# config.net
KiCad netlist of a schematic drawn in Altium Designer
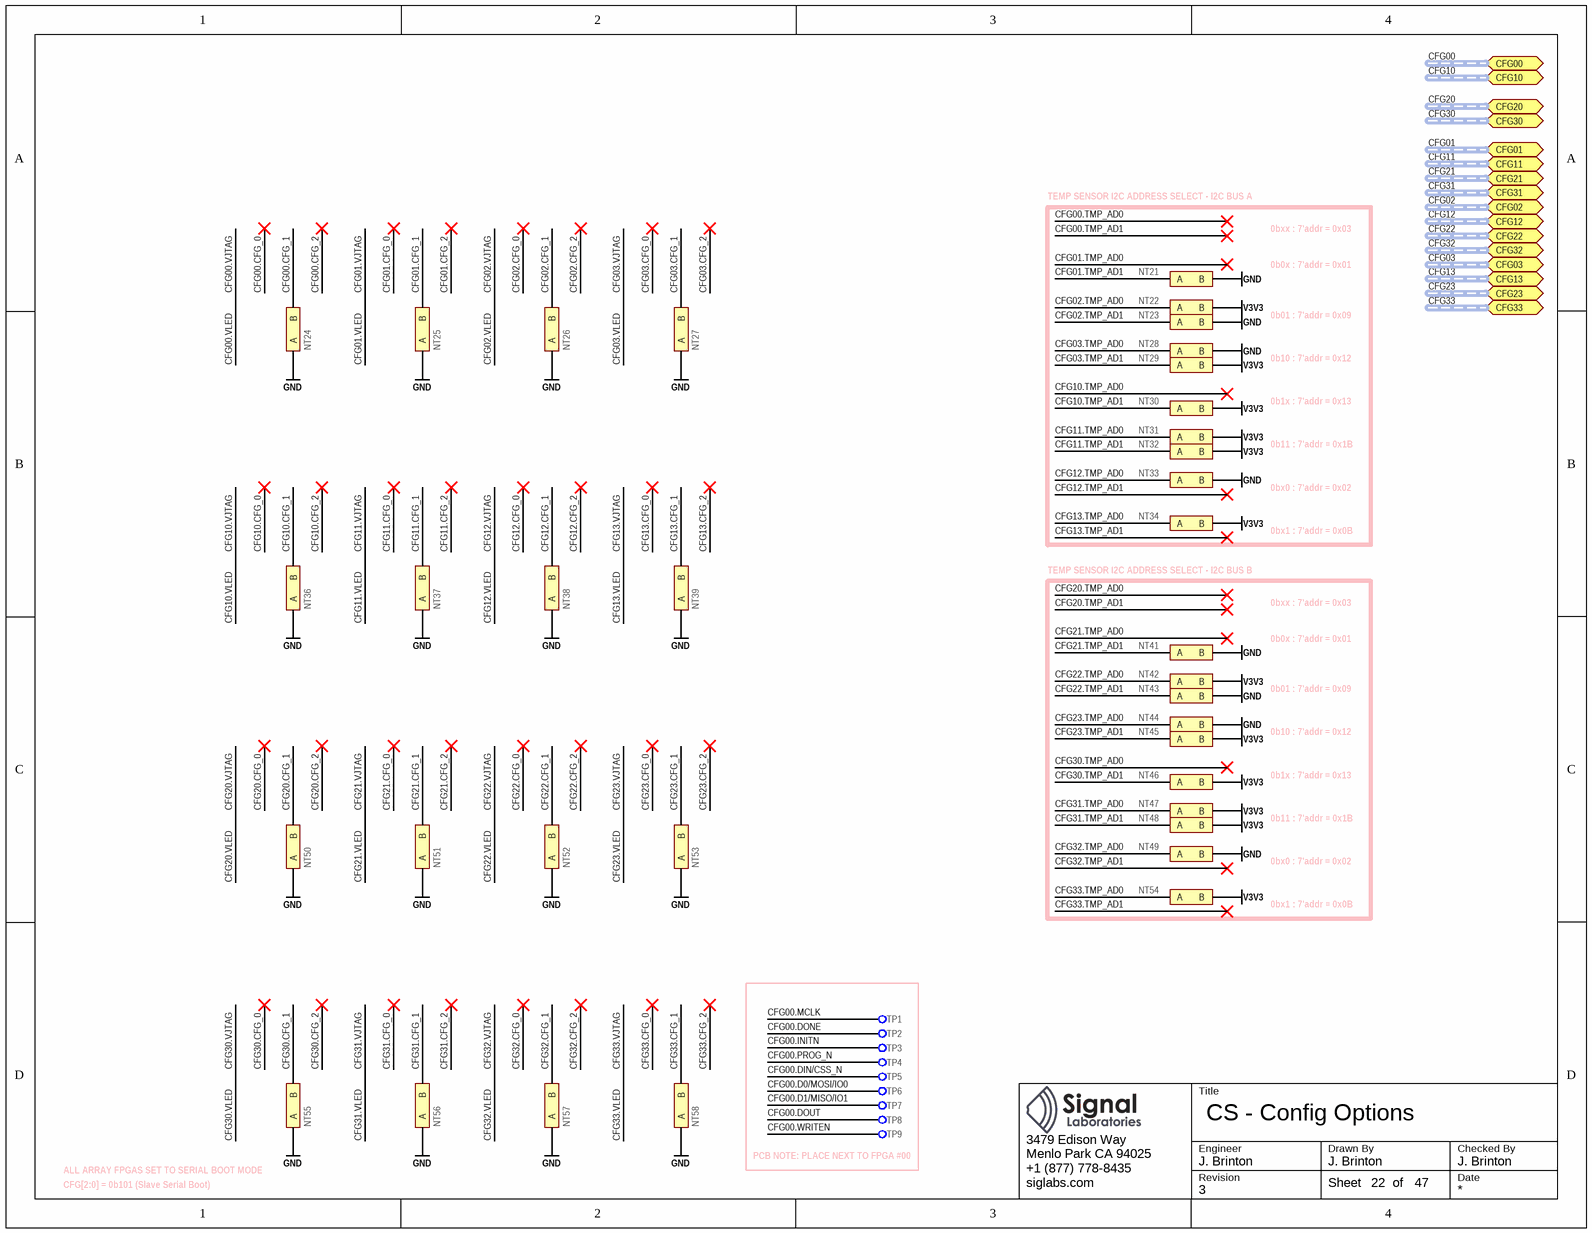
[diagram p0: config.SchDoc]

(export (version "E")
  (design (tool "Eeschema 10.0.6"))
  (components
    (comp (ref "NT21")
      (value "NET_TIE")
      (footprint "NET_TIE")
      (libsource (lib "copper_suicide") (part "NET_TIE"))
    )
    (comp (ref "NT22")
      (value "NET_TIE")
      (footprint "NET_TIE")
      (libsource (lib "copper_suicide") (part "NET_TIE"))
    )
    (comp (ref "NT23")
      (value "NET_TIE")
      (footprint "NET_TIE")
      (libsource (lib "copper_suicide") (part "NET_TIE"))
    )
    (comp (ref "NT24") (value "NET_TIE") (footprint "NET_TIE_400") (libsource (lib "") (part "NET_TIE_1")))
    (comp (ref "NT25") (value "NET_TIE") (footprint "NET_TIE_400") (libsource (lib "") (part "NET_TIE_1")))
    (comp (ref "NT26") (value "NET_TIE") (footprint "NET_TIE_400") (libsource (lib "") (part "NET_TIE_1")))
    (comp (ref "NT27") (value "NET_TIE") (footprint "NET_TIE_400") (libsource (lib "") (part "NET_TIE_1")))
    (comp (ref "NT28")
      (value "NET_TIE")
      (footprint "NET_TIE")
      (libsource (lib "copper_suicide") (part "NET_TIE"))
    )
    (comp (ref "NT29")
      (value "NET_TIE")
      (footprint "NET_TIE")
      (libsource (lib "copper_suicide") (part "NET_TIE"))
    )
    (comp (ref "NT30")
      (value "NET_TIE")
      (footprint "NET_TIE")
      (libsource (lib "copper_suicide") (part "NET_TIE"))
    )
    (comp (ref "NT31")
      (value "NET_TIE")
      (footprint "NET_TIE")
      (libsource (lib "copper_suicide") (part "NET_TIE"))
    )
    (comp (ref "NT32")
      (value "NET_TIE")
      (footprint "NET_TIE")
      (libsource (lib "copper_suicide") (part "NET_TIE"))
    )
    (comp (ref "NT33")
      (value "NET_TIE")
      (footprint "NET_TIE")
      (libsource (lib "copper_suicide") (part "NET_TIE"))
    )
    (comp (ref "NT34")
      (value "NET_TIE")
      (footprint "NET_TIE")
      (libsource (lib "copper_suicide") (part "NET_TIE"))
    )
    (comp (ref "NT36") (value "NET_TIE") (footprint "NET_TIE_400") (libsource (lib "") (part "NET_TIE_1")))
    (comp (ref "NT37") (value "NET_TIE") (footprint "NET_TIE_400") (libsource (lib "") (part "NET_TIE_1")))
    (comp (ref "NT38") (value "NET_TIE") (footprint "NET_TIE_400") (libsource (lib "") (part "NET_TIE_1")))
    (comp (ref "NT39") (value "NET_TIE") (footprint "NET_TIE_400") (libsource (lib "") (part "NET_TIE_1")))
    (comp (ref "NT41")
      (value "NET_TIE")
      (footprint "NET_TIE")
      (libsource (lib "copper_suicide") (part "NET_TIE"))
    )
    (comp (ref "NT42")
      (value "NET_TIE")
      (footprint "NET_TIE")
      (libsource (lib "copper_suicide") (part "NET_TIE"))
    )
    (comp (ref "NT43")
      (value "NET_TIE")
      (footprint "NET_TIE")
      (libsource (lib "copper_suicide") (part "NET_TIE"))
    )
    (comp (ref "NT44")
      (value "NET_TIE")
      (footprint "NET_TIE")
      (libsource (lib "copper_suicide") (part "NET_TIE"))
    )
    (comp (ref "NT45")
      (value "NET_TIE")
      (footprint "NET_TIE")
      (libsource (lib "copper_suicide") (part "NET_TIE"))
    )
    (comp (ref "NT46")
      (value "NET_TIE")
      (footprint "NET_TIE")
      (libsource (lib "copper_suicide") (part "NET_TIE"))
    )
    (comp (ref "NT47")
      (value "NET_TIE")
      (footprint "NET_TIE")
      (libsource (lib "copper_suicide") (part "NET_TIE"))
    )
    (comp (ref "NT48")
      (value "NET_TIE")
      (footprint "NET_TIE")
      (libsource (lib "copper_suicide") (part "NET_TIE"))
    )
    (comp (ref "NT49")
      (value "NET_TIE")
      (footprint "NET_TIE")
      (libsource (lib "copper_suicide") (part "NET_TIE"))
    )
    (comp (ref "NT50") (value "NET_TIE") (footprint "NET_TIE_400") (libsource (lib "") (part "NET_TIE_1")))
    (comp (ref "NT51") (value "NET_TIE") (footprint "NET_TIE_400") (libsource (lib "") (part "NET_TIE_1")))
    (comp (ref "NT52") (value "NET_TIE") (footprint "NET_TIE_400") (libsource (lib "") (part "NET_TIE_1")))
    (comp (ref "NT53") (value "NET_TIE") (footprint "NET_TIE_400") (libsource (lib "") (part "NET_TIE_1")))
    (comp (ref "NT54")
      (value "NET_TIE")
      (footprint "NET_TIE")
      (libsource (lib "copper_suicide") (part "NET_TIE"))
    )
    (comp (ref "NT55") (value "NET_TIE") (footprint "NET_TIE_400") (libsource (lib "") (part "NET_TIE_1")))
    (comp (ref "NT56") (value "NET_TIE") (footprint "NET_TIE_400") (libsource (lib "") (part "NET_TIE_1")))
    (comp (ref "NT57") (value "NET_TIE") (footprint "NET_TIE_400") (libsource (lib "") (part "NET_TIE_1")))
    (comp (ref "NT58") (value "NET_TIE") (footprint "NET_TIE_400") (libsource (lib "") (part "NET_TIE_1")))
    (comp (ref "TP1")
      (value "5000")
      (footprint "TEST_POINT_SMD_10")
      (description "Thruhole Miniature Test Point")
      (fields (field (name "MANUFACTURER") "Keystone Electronics Corp"))
      (libsource (lib "generic") (part "TEST_POINT"))
    )
    (comp (ref "TP2")
      (value "5000")
      (footprint "TEST_POINT_SMD_10")
      (description "Thruhole Miniature Test Point")
      (fields (field (name "MANUFACTURER") "Keystone Electronics Corp"))
      (libsource (lib "generic") (part "TEST_POINT"))
    )
    (comp (ref "TP3")
      (value "5000")
      (footprint "TEST_POINT_SMD_10")
      (description "Thruhole Miniature Test Point")
      (fields (field (name "MANUFACTURER") "Keystone Electronics Corp"))
      (libsource (lib "generic") (part "TEST_POINT"))
    )
    (comp (ref "TP4")
      (value "5000")
      (footprint "TEST_POINT_SMD_10")
      (description "Thruhole Miniature Test Point")
      (fields (field (name "MANUFACTURER") "Keystone Electronics Corp"))
      (libsource (lib "generic") (part "TEST_POINT"))
    )
    (comp (ref "TP5")
      (value "5000")
      (footprint "TEST_POINT_SMD_10")
      (description "Thruhole Miniature Test Point")
      (fields (field (name "MANUFACTURER") "Keystone Electronics Corp"))
      (libsource (lib "generic") (part "TEST_POINT"))
    )
    (comp (ref "TP6")
      (value "5000")
      (footprint "TEST_POINT_SMD_10")
      (description "Thruhole Miniature Test Point")
      (fields (field (name "MANUFACTURER") "Keystone Electronics Corp"))
      (libsource (lib "generic") (part "TEST_POINT"))
    )
    (comp (ref "TP7")
      (value "5000")
      (footprint "TEST_POINT_SMD_10")
      (description "Thruhole Miniature Test Point")
      (fields (field (name "MANUFACTURER") "Keystone Electronics Corp"))
      (libsource (lib "generic") (part "TEST_POINT"))
    )
    (comp (ref "TP8")
      (value "5000")
      (footprint "TEST_POINT_SMD_10")
      (description "Thruhole Miniature Test Point")
      (fields (field (name "MANUFACTURER") "Keystone Electronics Corp"))
      (libsource (lib "generic") (part "TEST_POINT"))
    )
    (comp (ref "TP9")
      (value "5000")
      (footprint "TEST_POINT_SMD_10")
      (description "Thruhole Miniature Test Point")
      (fields (field (name "MANUFACTURER") "Keystone Electronics Corp"))
      (libsource (lib "generic") (part "TEST_POINT"))
    )
  )
  (nets
    (net (code "18") (name "/CFG00.CFG_1") (class "Default")
      (node (ref "NT24") (pin "B") (pinfunction "B_B") (pintype "passive"))
    )
    (net (code "20") (name "/CFG00.D0{slash}MOSI{slash}IO0") (class "Default")
      (node (ref "TP6") (pin "1") (pinfunction "1_1") (pintype "passive"))
    )
    (net (code "21") (name "/CFG00.D1{slash}MISO{slash}IO1") (class "Default")
      (node (ref "TP7") (pin "1") (pinfunction "1_1") (pintype "passive"))
    )
    (net (code "22") (name "/CFG00.DIN{slash}CSS_N") (class "Default")
      (node (ref "TP5") (pin "1") (pinfunction "1_1") (pintype "passive"))
    )
    (net (code "23") (name "/CFG00.DONE") (class "Default")
      (node (ref "TP2") (pin "1") (pinfunction "1_1") (pintype "passive"))
    )
    (net (code "24") (name "/CFG00.DOUT") (class "Default")
      (node (ref "TP8") (pin "1") (pinfunction "1_1") (pintype "passive"))
    )
    (net (code "25") (name "/CFG00.INITN") (class "Default")
      (node (ref "TP3") (pin "1") (pinfunction "1_1") (pintype "passive"))
    )
    (net (code "26") (name "/CFG00.MCLK") (class "Default")
      (node (ref "TP1") (pin "1") (pinfunction "1_1") (pintype "passive"))
    )
    (net (code "27") (name "/CFG00.PROG_N") (class "Default")
      (node (ref "TP4") (pin "1") (pinfunction "1_1") (pintype "passive"))
    )
    (net (code "31") (name "/CFG00.WRITEN") (class "Default")
      (node (ref "TP9") (pin "1") (pinfunction "1_1") (pintype "passive"))
    )
    (net (code "33") (name "/CFG01.CFG_1") (class "Default")
      (node (ref "NT25") (pin "B") (pinfunction "B_B") (pintype "passive"))
    )
    (net (code "36") (name "/CFG01.TMP_AD1") (class "Default")
      (node (ref "NT21") (pin "A") (pinfunction "A_A") (pintype "passive"))
    )
    (net (code "39") (name "/CFG02.CFG_1") (class "Default")
      (node (ref "NT26") (pin "B") (pinfunction "B_B") (pintype "passive"))
    )
    (net (code "41") (name "/CFG02.TMP_AD0") (class "Default")
      (node (ref "NT22") (pin "A") (pinfunction "A_A") (pintype "passive"))
    )
    (net (code "42") (name "/CFG02.TMP_AD1") (class "Default")
      (node (ref "NT23") (pin "A") (pinfunction "A_A") (pintype "passive"))
    )
    (net (code "45") (name "/CFG03.CFG_1") (class "Default")
      (node (ref "NT27") (pin "B") (pinfunction "B_B") (pintype "passive"))
    )
    (net (code "47") (name "/CFG03.TMP_AD0") (class "Default")
      (node (ref "NT28") (pin "A") (pinfunction "A_A") (pintype "passive"))
    )
    (net (code "48") (name "/CFG03.TMP_AD1") (class "Default")
      (node (ref "NT29") (pin "A") (pinfunction "A_A") (pintype "passive"))
    )
    (net (code "51") (name "/CFG10.CFG_1") (class "Default")
      (node (ref "NT36") (pin "B") (pinfunction "B_B") (pintype "passive"))
    )
    (net (code "54") (name "/CFG10.TMP_AD1") (class "Default")
      (node (ref "NT30") (pin "A") (pinfunction "A_A") (pintype "passive"))
    )
    (net (code "57") (name "/CFG11.CFG_1") (class "Default")
      (node (ref "NT37") (pin "B") (pinfunction "B_B") (pintype "passive"))
    )
    (net (code "59") (name "/CFG11.TMP_AD0") (class "Default")
      (node (ref "NT31") (pin "A") (pinfunction "A_A") (pintype "passive"))
    )
    (net (code "60") (name "/CFG11.TMP_AD1") (class "Default")
      (node (ref "NT32") (pin "A") (pinfunction "A_A") (pintype "passive"))
    )
    (net (code "63") (name "/CFG12.CFG_1") (class "Default")
      (node (ref "NT38") (pin "B") (pinfunction "B_B") (pintype "passive"))
    )
    (net (code "65") (name "/CFG12.TMP_AD0") (class "Default")
      (node (ref "NT33") (pin "A") (pinfunction "A_A") (pintype "passive"))
    )
    (net (code "69") (name "/CFG13.CFG_1") (class "Default")
      (node (ref "NT39") (pin "B") (pinfunction "B_B") (pintype "passive"))
    )
    (net (code "71") (name "/CFG13.TMP_AD0") (class "Default")
      (node (ref "NT34") (pin "A") (pinfunction "A_A") (pintype "passive"))
    )
    (net (code "75") (name "/CFG20.CFG_1") (class "Default")
      (node (ref "NT50") (pin "B") (pinfunction "B_B") (pintype "passive"))
    )
    (net (code "81") (name "/CFG21.CFG_1") (class "Default")
      (node (ref "NT51") (pin "B") (pinfunction "B_B") (pintype "passive"))
    )
    (net (code "84") (name "/CFG21.TMP_AD1") (class "Default")
      (node (ref "NT41") (pin "A") (pinfunction "A_A") (pintype "passive"))
    )
    (net (code "87") (name "/CFG22.CFG_1") (class "Default")
      (node (ref "NT52") (pin "B") (pinfunction "B_B") (pintype "passive"))
    )
    (net (code "89") (name "/CFG22.TMP_AD0") (class "Default")
      (node (ref "NT42") (pin "A") (pinfunction "A_A") (pintype "passive"))
    )
    (net (code "90") (name "/CFG22.TMP_AD1") (class "Default")
      (node (ref "NT43") (pin "A") (pinfunction "A_A") (pintype "passive"))
    )
    (net (code "93") (name "/CFG23.CFG_1") (class "Default")
      (node (ref "NT53") (pin "B") (pinfunction "B_B") (pintype "passive"))
    )
    (net (code "95") (name "/CFG23.TMP_AD0") (class "Default")
      (node (ref "NT44") (pin "A") (pinfunction "A_A") (pintype "passive"))
    )
    (net (code "96") (name "/CFG23.TMP_AD1") (class "Default")
      (node (ref "NT45") (pin "A") (pinfunction "A_A") (pintype "passive"))
    )
    (net (code "99") (name "/CFG30.CFG_1") (class "Default")
      (node (ref "NT55") (pin "B") (pinfunction "B_B") (pintype "passive"))
    )
    (net (code "102") (name "/CFG30.TMP_AD1") (class "Default")
      (node (ref "NT46") (pin "A") (pinfunction "A_A") (pintype "passive"))
    )
    (net (code "105") (name "/CFG31.CFG_1") (class "Default")
      (node (ref "NT56") (pin "B") (pinfunction "B_B") (pintype "passive"))
    )
    (net (code "107") (name "/CFG31.TMP_AD0") (class "Default")
      (node (ref "NT47") (pin "A") (pinfunction "A_A") (pintype "passive"))
    )
    (net (code "108") (name "/CFG31.TMP_AD1") (class "Default")
      (node (ref "NT48") (pin "A") (pinfunction "A_A") (pintype "passive"))
    )
    (net (code "111") (name "/CFG32.CFG_1") (class "Default")
      (node (ref "NT57") (pin "B") (pinfunction "B_B") (pintype "passive"))
    )
    (net (code "113") (name "/CFG32.TMP_AD0") (class "Default")
      (node (ref "NT49") (pin "A") (pinfunction "A_A") (pintype "passive"))
    )
    (net (code "117") (name "/CFG33.CFG_1") (class "Default")
      (node (ref "NT58") (pin "B") (pinfunction "B_B") (pintype "passive"))
    )
    (net (code "119") (name "/CFG33.TMP_AD0") (class "Default")
      (node (ref "NT54") (pin "A") (pinfunction "A_A") (pintype "passive"))
    )
    (net (code "138") (name "GND") (class "Default")
      (node (ref "NT21") (pin "B") (pinfunction "B_B") (pintype "passive"))
      (node (ref "NT23") (pin "B") (pinfunction "B_B") (pintype "passive"))
      (node (ref "NT24") (pin "A") (pinfunction "A_A") (pintype "passive"))
      (node (ref "NT25") (pin "A") (pinfunction "A_A") (pintype "passive"))
      (node (ref "NT26") (pin "A") (pinfunction "A_A") (pintype "passive"))
      (node (ref "NT27") (pin "A") (pinfunction "A_A") (pintype "passive"))
      (node (ref "NT28") (pin "B") (pinfunction "B_B") (pintype "passive"))
      (node (ref "NT33") (pin "B") (pinfunction "B_B") (pintype "passive"))
      (node (ref "NT36") (pin "A") (pinfunction "A_A") (pintype "passive"))
      (node (ref "NT37") (pin "A") (pinfunction "A_A") (pintype "passive"))
      (node (ref "NT38") (pin "A") (pinfunction "A_A") (pintype "passive"))
      (node (ref "NT39") (pin "A") (pinfunction "A_A") (pintype "passive"))
      (node (ref "NT41") (pin "B") (pinfunction "B_B") (pintype "passive"))
      (node (ref "NT43") (pin "B") (pinfunction "B_B") (pintype "passive"))
      (node (ref "NT44") (pin "B") (pinfunction "B_B") (pintype "passive"))
      (node (ref "NT49") (pin "B") (pinfunction "B_B") (pintype "passive"))
      (node (ref "NT50") (pin "A") (pinfunction "A_A") (pintype "passive"))
      (node (ref "NT51") (pin "A") (pinfunction "A_A") (pintype "passive"))
      (node (ref "NT52") (pin "A") (pinfunction "A_A") (pintype "passive"))
      (node (ref "NT53") (pin "A") (pinfunction "A_A") (pintype "passive"))
      (node (ref "NT55") (pin "A") (pinfunction "A_A") (pintype "passive"))
      (node (ref "NT56") (pin "A") (pinfunction "A_A") (pintype "passive"))
      (node (ref "NT57") (pin "A") (pinfunction "A_A") (pintype "passive"))
      (node (ref "NT58") (pin "A") (pinfunction "A_A") (pintype "passive"))
    )
    (net (code "139") (name "V3V3") (class "Default")
      (node (ref "NT22") (pin "B") (pinfunction "B_B") (pintype "passive"))
      (node (ref "NT29") (pin "B") (pinfunction "B_B") (pintype "passive"))
      (node (ref "NT30") (pin "B") (pinfunction "B_B") (pintype "passive"))
      (node (ref "NT31") (pin "B") (pinfunction "B_B") (pintype "passive"))
      (node (ref "NT32") (pin "B") (pinfunction "B_B") (pintype "passive"))
      (node (ref "NT34") (pin "B") (pinfunction "B_B") (pintype "passive"))
      (node (ref "NT42") (pin "B") (pinfunction "B_B") (pintype "passive"))
      (node (ref "NT45") (pin "B") (pinfunction "B_B") (pintype "passive"))
      (node (ref "NT46") (pin "B") (pinfunction "B_B") (pintype "passive"))
      (node (ref "NT47") (pin "B") (pinfunction "B_B") (pintype "passive"))
      (node (ref "NT48") (pin "B") (pinfunction "B_B") (pintype "passive"))
      (node (ref "NT54") (pin "B") (pinfunction "B_B") (pintype "passive"))
    )
  )
)
